# STM32L4_Lora.net
KiCad netlist of a schematic drawn in EAGLE
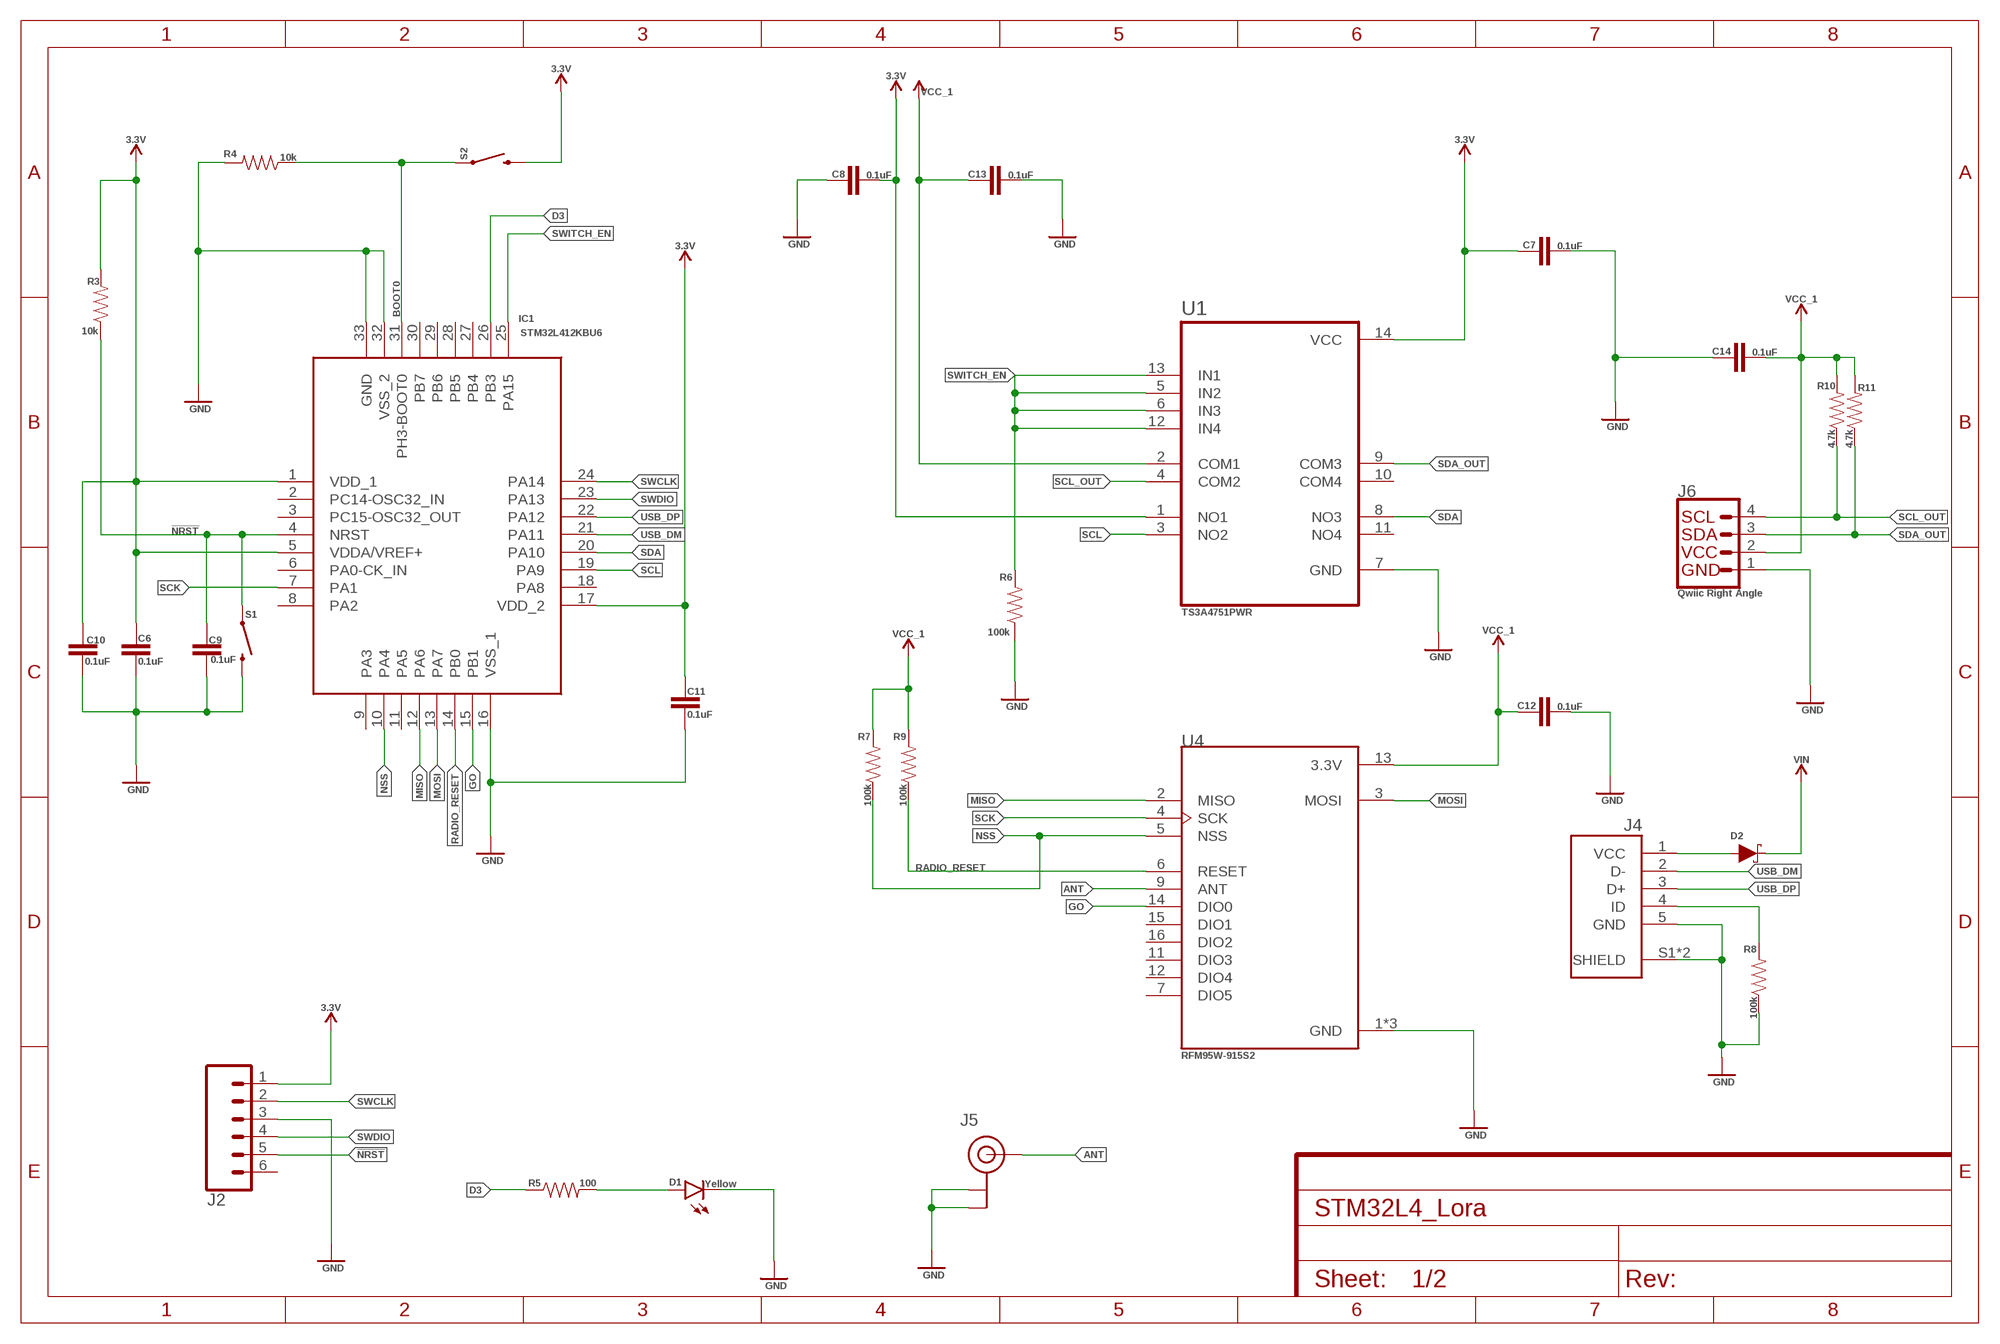
[diagram p0: schematic, sheet 1]
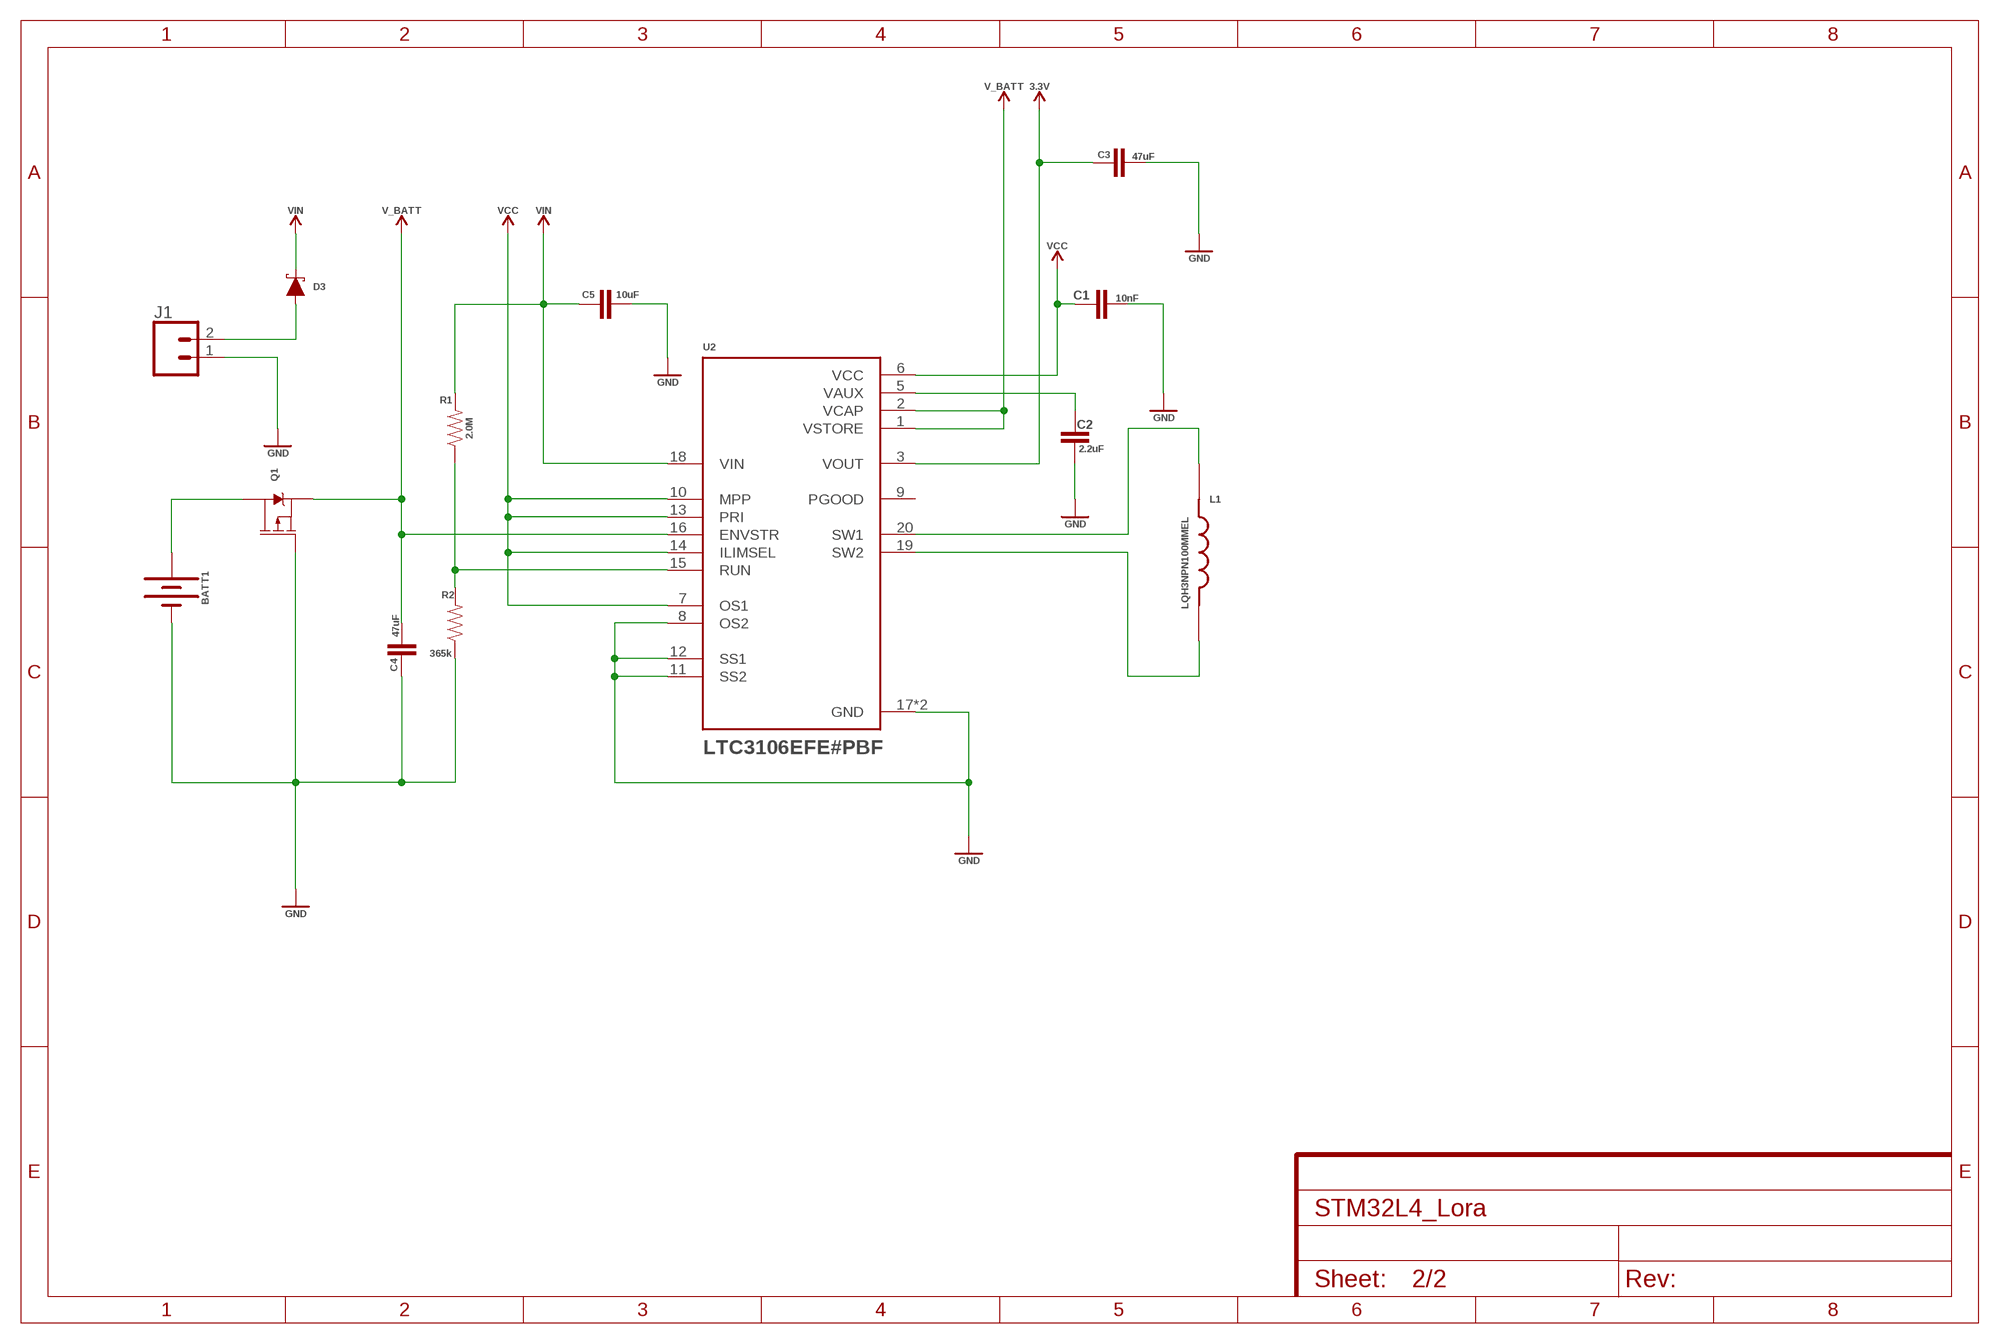
[diagram p1: schematic, sheet 2]

(export (version "E")
  (design (tool "Eeschema 10.0.6"))
  (components
    (comp (ref "C6")
      (value "0.1uF")
      (footprint "eagle-import:0603")
      (libsource (lib "eagle-import") (part "0.1UF-0603-25V-(+80/-20%)"))
    )
    (comp (ref "C7")
      (value "0.1uF")
      (footprint "eagle-import:0603")
      (libsource (lib "eagle-import") (part "0.1UF-0603-25V-(+80/-20%)"))
    )
    (comp (ref "C8")
      (value "0.1uF")
      (footprint "eagle-import:0603")
      (libsource (lib "eagle-import") (part "0.1UF-0603-25V-(+80/-20%)"))
    )
    (comp (ref "C9")
      (value "0.1uF")
      (footprint "eagle-import:0603")
      (libsource (lib "eagle-import") (part "0.1UF-0603-25V-(+80/-20%)"))
    )
    (comp (ref "C10")
      (value "0.1uF")
      (footprint "eagle-import:0603")
      (libsource (lib "eagle-import") (part "0.1UF-0603-25V-(+80/-20%)"))
    )
    (comp (ref "C11")
      (value "0.1uF")
      (footprint "eagle-import:0603")
      (libsource (lib "eagle-import") (part "0.1UF-0603-25V-(+80/-20%)"))
    )
    (comp (ref "C12")
      (value "0.1uF")
      (footprint "eagle-import:0603")
      (libsource (lib "eagle-import") (part "0.1UF-0603-25V-(+80/-20%)"))
    )
    (comp (ref "C13")
      (value "0.1uF")
      (footprint "eagle-import:0603")
      (libsource (lib "eagle-import") (part "0.1UF-0603-25V-(+80/-20%)"))
    )
    (comp (ref "C14")
      (value "0.1uF")
      (footprint "eagle-import:0603")
      (libsource (lib "eagle-import") (part "0.1UF-0603-25V-(+80/-20%)"))
    )
    (comp (ref "D1")
      (value "Yellow")
      (footprint "eagle-import:LED-0603")
      (libsource (lib "eagle-import") (part "LED-YELLOW0603"))
    )
    (comp (ref "D2")
      (value "120mA/40V/370mV")
      (footprint "eagle-import:SOD-523")
      (libsource (lib "eagle-import") (part "DIODE-SCHOTTKY-RB751S40"))
    )
    (comp (ref "IC1")
      (value "STM32L412KBU6")
      (footprint "eagle-import:QFN50P500X500X60-33N")
      (fields (field (name "MOUSER_PART_NUMBER") "511-STM32L412KBU6"))
      (libsource (lib "eagle-import") (part "STM32L412KBU6"))
    )
    (comp (ref "J2")
      (value "CONN_06LOCK_LONGPADS")
      (footprint "eagle-import:1X06_LOCK_LONGPADS")
      (libsource (lib "eagle-import") (part "CONN_06LOCK_LONGPADS"))
    )
    (comp (ref "J4")
      (value "USB3131-30-0230-A_REVB")
      (footprint "eagle-import:GCT_USB3131-30-0230-A_REVB")
      (fields (field (name "MF") "Global Connector Technology") (field (name "MP") "USB3131-30-0230-A"))
      (libsource (lib "eagle-import") (part "USB3131-30-0230-A_REVB"))
    )
    (comp (ref "J5")
      (value "U.FL")
      (footprint "eagle-import:U.FL")
      (libsource (lib "eagle-import") (part "U.FL"))
    )
    (comp (ref "J6")
      (value "Qwiic Right Angle")
      (footprint "eagle-import:1X04_1MM_RA")
      (libsource (lib "eagle-import") (part "I2C_STANDARDQWIIC"))
    )
    (comp (ref "R3")
      (value "10k")
      (footprint "eagle-import:0603")
      (libsource (lib "eagle-import") (part "10KOHM-0603-1/10W-1%"))
    )
    (comp (ref "R4")
      (value "10k")
      (footprint "eagle-import:0603")
      (libsource (lib "eagle-import") (part "10KOHM-0603-1/10W-1%"))
    )
    (comp (ref "R5")
      (value "100")
      (footprint "eagle-import:0603")
      (libsource (lib "eagle-import") (part "100OHM-0603-1/4W-5%"))
    )
    (comp (ref "R6")
      (value "100k")
      (footprint "eagle-import:0603")
      (libsource (lib "eagle-import") (part "100KOHM-0603-1/10W-1%"))
    )
    (comp (ref "R7")
      (value "100k")
      (footprint "eagle-import:0603")
      (libsource (lib "eagle-import") (part "100KOHM-0603-1/10W-1%"))
    )
    (comp (ref "R8")
      (value "100k")
      (footprint "eagle-import:0603")
      (libsource (lib "eagle-import") (part "100KOHM-0603-1/10W-1%"))
    )
    (comp (ref "R9")
      (value "100k")
      (footprint "eagle-import:0603")
      (libsource (lib "eagle-import") (part "100KOHM-0603-1/10W-1%"))
    )
    (comp (ref "R10")
      (value "4.7k")
      (footprint "eagle-import:0603")
      (libsource (lib "eagle-import") (part "4.7KOHM-0603-1/10W-1%"))
    )
    (comp (ref "R11")
      (value "4.7k")
      (footprint "eagle-import:0603")
      (libsource (lib "eagle-import") (part "4.7KOHM-0603-1/10W-1%"))
    )
    (comp (ref "S1")
      (value "MOMENTARY-SWITCH-SPST-SMD-4.6X2.8MM")
      (footprint "eagle-import:TACTILE_SWITCH_SMD_4.6X2.8MM")
      (libsource (lib "eagle-import") (part "MOMENTARY-SWITCH-SPST-SMD-4.6X2.8MM"))
    )
    (comp (ref "S2")
      (value "MOMENTARY-SWITCH-SPST-SMD-4.6X2.8MM")
      (footprint "eagle-import:TACTILE_SWITCH_SMD_4.6X2.8MM")
      (libsource (lib "eagle-import") (part "MOMENTARY-SWITCH-SPST-SMD-4.6X2.8MM"))
    )
    (comp (ref "U1")
      (value "TS3A4751PWR")
      (footprint "eagle-import:SOP65P640X120-14N")
      (fields (field (name "DIGI-KEY_PART_NUMBER") "296-20700-1-ND") (field (name "MF") "Texas Instruments"))
      (libsource (lib "eagle-import") (part "TS3A4751PWR"))
    )
    (comp (ref "U4")
      (value "RFM95W-915S2")
      (footprint "eagle-import:XCVR_RFM95W-915S2")
      (fields (field (name "MF") "RF Solutions"))
      (libsource (lib "eagle-import") (part "RFM95W-915S2"))
    )
    (comp (ref "BATT1")
      (value "KEYSTONE_54KEYSTONE_2")
      (footprint "eagle-import:KEYSTONE_V2")
      (libsource (lib "eagle-import") (part "KEYSTONE_54KEYSTONE_2"))
    )
    (comp (ref "C1")
      (value "10nF")
      (footprint "eagle-import:0603")
      (libsource (lib "eagle-import") (part "10NF-0603-50V-10%"))
    )
    (comp (ref "C2")
      (value "2.2uF")
      (footprint "eagle-import:0603")
      (libsource (lib "eagle-import") (part "2.2UF-0603-10V-20%"))
    )
    (comp (ref "C3")
      (value "47uF")
      (footprint "eagle-import:0603")
      (libsource (lib "eagle-import") (part "4.7UF0603"))
    )
    (comp (ref "C4")
      (value "47uF")
      (footprint "eagle-import:0603")
      (libsource (lib "eagle-import") (part "4.7UF0603"))
    )
    (comp (ref "C5")
      (value "10uF")
      (footprint "eagle-import:0603")
      (libsource (lib "eagle-import") (part "10UF-0603-6.3V-20%"))
    )
    (comp (ref "D3")
      (value "120mA/40V/370mV")
      (footprint "eagle-import:SOD-523")
      (libsource (lib "eagle-import") (part "DIODE-SCHOTTKY-RB751S40"))
    )
    (comp (ref "J1")
      (value "CONN_023.5MM")
      (footprint "eagle-import:SCREWTERMINAL-3.5MM-2")
      (libsource (lib "eagle-import") (part "CONN_023.5MM"))
    )
    (comp (ref "L1")
      (value "LQH3NPN100MMEL")
      (footprint "eagle-import:IND_LQH3NPN100MMEL")
      (fields (field (name "DIGI-KEY_PART_NUMBER") "490-15945-1-ND") (field (name "MF") "Murata"))
      (libsource (lib "eagle-import") (part "LQH3NPN100MMEL"))
    )
    (comp (ref "Q1")
      (value "2.5A/30V/105mΩ")
      (footprint "eagle-import:SOT23-3")
      (libsource (lib "eagle-import") (part "MOSFET_PCH-DMG2307L"))
    )
    (comp (ref "R1")
      (value "2.0M")
      (footprint "eagle-import:0603")
      (libsource (lib "eagle-import") (part "2MOHMS-0603-1/10W-1%"))
    )
    (comp (ref "R2")
      (value "365k")
      (footprint "eagle-import:0603")
      (libsource (lib "eagle-import") (part "390KOHM-0603-1/10W-1%"))
    )
    (comp (ref "U2")
      (value "LTC3106EFE#PBF")
      (footprint "eagle-import:SOP65P640X120-21N")
      (fields (field (name "MF") "Analog Devices"))
      (libsource (lib "eagle-import") (part "LTC3106EFE#PBF"))
    )
  )
  (nets
    (net (code "1") (name "3.3V") (class "Default")
      (node (ref "C10") (pin "1") (pinfunction "1_1") (pintype "passive"))
      (node (ref "C11") (pin "1") (pinfunction "1_1") (pintype "passive"))
      (node (ref "C3") (pin "1") (pinfunction "1_1") (pintype "passive"))
      (node (ref "C6") (pin "1") (pinfunction "1_1") (pintype "passive"))
      (node (ref "C7") (pin "1") (pinfunction "1_1") (pintype "passive"))
      (node (ref "C8") (pin "2") (pinfunction "2_2") (pintype "passive"))
      (node (ref "IC1") (pin "1") (pinfunction "VDD_1_1") (pintype "bidirectional"))
      (node (ref "IC1") (pin "17") (pinfunction "VDD_2_17") (pintype "bidirectional"))
      (node (ref "IC1") (pin "5") (pinfunction "VDDA/VREF+_5") (pintype "bidirectional"))
      (node (ref "J2") (pin "1") (pinfunction "1_1") (pintype "passive"))
      (node (ref "R3") (pin "2") (pinfunction "2_2") (pintype "passive"))
      (node (ref "S2") (pin "3") (pinfunction "2_3") (pintype "passive"))
      (node (ref "S2") (pin "4") (pinfunction "2_4") (pintype "passive"))
      (node (ref "U1") (pin "1") (pinfunction "NO1_1") (pintype "bidirectional"))
      (node (ref "U1") (pin "14") (pinfunction "VCC_14") (pintype "power_in"))
      (node (ref "U2") (pin "3") (pinfunction "VOUT_3") (pintype "output"))
    )
    (net (code "2") (name "ANT") (class "Default")
      (node (ref "J5") (pin "FEED") (pinfunction "SIGNAL_FEED") (pintype "bidirectional"))
      (node (ref "U4") (pin "9") (pinfunction "ANT_9") (pintype "bidirectional"))
    )
    (net (code "3") (name "BOOT0") (class "Default")
      (node (ref "IC1") (pin "31") (pinfunction "PH3-BOOT0_31") (pintype "bidirectional"))
      (node (ref "R4") (pin "1") (pinfunction "1_1") (pintype "passive"))
      (node (ref "S2") (pin "1") (pinfunction "1_1") (pintype "passive"))
      (node (ref "S2") (pin "2") (pinfunction "1_2") (pintype "passive"))
    )
    (net (code "4") (name "D3") (class "Default")
      (node (ref "IC1") (pin "26") (pinfunction "PB3_26") (pintype "bidirectional"))
      (node (ref "R5") (pin "1") (pinfunction "1_1") (pintype "passive"))
    )
    (net (code "5") (name "GND") (class "Default")
      (node (ref "BATT1") (pin "P$4") (pinfunction "-_P$4") (pintype "power_in"))
      (node (ref "BATT1") (pin "P$5") (pinfunction "-_P$5") (pintype "power_in"))
      (node (ref "BATT1") (pin "P$6") (pinfunction "-_P$6") (pintype "power_in"))
      (node (ref "C1") (pin "2") (pinfunction "2_2") (pintype "passive"))
      (node (ref "C10") (pin "2") (pinfunction "2_2") (pintype "passive"))
      (node (ref "C11") (pin "2") (pinfunction "2_2") (pintype "passive"))
      (node (ref "C12") (pin "2") (pinfunction "2_2") (pintype "passive"))
      (node (ref "C13") (pin "2") (pinfunction "2_2") (pintype "passive"))
      (node (ref "C14") (pin "1") (pinfunction "1_1") (pintype "passive"))
      (node (ref "C2") (pin "2") (pinfunction "2_2") (pintype "passive"))
      (node (ref "C3") (pin "2") (pinfunction "2_2") (pintype "passive"))
      (node (ref "C4") (pin "1") (pinfunction "1_1") (pintype "passive"))
      (node (ref "C5") (pin "2") (pinfunction "2_2") (pintype "passive"))
      (node (ref "C6") (pin "2") (pinfunction "2_2") (pintype "passive"))
      (node (ref "C7") (pin "2") (pinfunction "2_2") (pintype "passive"))
      (node (ref "C8") (pin "1") (pinfunction "1_1") (pintype "passive"))
      (node (ref "C9") (pin "2") (pinfunction "2_2") (pintype "passive"))
      (node (ref "D1") (pin "C") (pinfunction "C_C") (pintype "passive"))
      (node (ref "IC1") (pin "16") (pinfunction "VSS_1_16") (pintype "bidirectional"))
      (node (ref "IC1") (pin "32") (pinfunction "VSS_2_32") (pintype "bidirectional"))
      (node (ref "IC1") (pin "33") (pinfunction "GND_33") (pintype "bidirectional"))
      (node (ref "J1") (pin "1") (pinfunction "1_1") (pintype "passive"))
      (node (ref "J2") (pin "3") (pinfunction "3_3") (pintype "passive"))
      (node (ref "J4") (pin "5") (pinfunction "GND_5") (pintype "power_in"))
      (node (ref "J4") (pin "S1") (pinfunction "SHIELD_S1") (pintype "passive"))
      (node (ref "J4") (pin "S2") (pinfunction "SHIELD_S2") (pintype "passive"))
      (node (ref "J5") (pin "1") (pinfunction "GND_1") (pintype "bidirectional"))
      (node (ref "J5") (pin "2") (pinfunction "GND_2") (pintype "bidirectional"))
      (node (ref "J6") (pin "1") (pinfunction "1_1") (pintype "power_in"))
      (node (ref "Q1") (pin "1") (pinfunction "G_1") (pintype "bidirectional"))
      (node (ref "R2") (pin "1") (pinfunction "1_1") (pintype "passive"))
      (node (ref "R4") (pin "2") (pinfunction "2_2") (pintype "passive"))
      (node (ref "R6") (pin "1") (pinfunction "1_1") (pintype "passive"))
      (node (ref "R8") (pin "1") (pinfunction "1_1") (pintype "passive"))
      (node (ref "S1") (pin "3") (pinfunction "2_3") (pintype "passive"))
      (node (ref "S1") (pin "4") (pinfunction "2_4") (pintype "passive"))
      (node (ref "U1") (pin "7") (pinfunction "GND_7") (pintype "power_in"))
      (node (ref "U2") (pin "11") (pinfunction "SS2_11") (pintype "input"))
      (node (ref "U2") (pin "12") (pinfunction "SS1_12") (pintype "input"))
      (node (ref "U2") (pin "17") (pinfunction "GND_17") (pintype "power_in"))
      (node (ref "U2") (pin "21") (pinfunction "GND_21") (pintype "power_in"))
      (node (ref "U2") (pin "8") (pinfunction "OS2_8") (pintype "input"))
      (node (ref "U4") (pin "1") (pinfunction "GND_1") (pintype "power_in"))
      (node (ref "U4") (pin "10") (pinfunction "GND_10") (pintype "power_in"))
      (node (ref "U4") (pin "8") (pinfunction "GND_8") (pintype "power_in"))
    )
    (net (code "6") (name "GO") (class "Default")
      (node (ref "IC1") (pin "15") (pinfunction "PB1_15") (pintype "bidirectional"))
      (node (ref "U4") (pin "14") (pinfunction "DIO0_14") (pintype "bidirectional"))
    )
    (net (code "7") (name "MISO") (class "Default")
      (node (ref "IC1") (pin "12") (pinfunction "PA6_12") (pintype "bidirectional"))
      (node (ref "U4") (pin "2") (pinfunction "MISO_2") (pintype "input"))
    )
    (net (code "8") (name "MOSI") (class "Default")
      (node (ref "IC1") (pin "13") (pinfunction "PA7_13") (pintype "bidirectional"))
      (node (ref "U4") (pin "3") (pinfunction "MOSI_3") (pintype "output"))
    )
    (net (code "9") (name "NSS") (class "Default")
      (node (ref "IC1") (pin "10") (pinfunction "PA4_10") (pintype "bidirectional"))
      (node (ref "R7") (pin "1") (pinfunction "1_1") (pintype "passive"))
      (node (ref "U4") (pin "5") (pinfunction "NSS_5") (pintype "input"))
    )
    (net (code "10") (name "Net-(D1-PadA)") (class "Default")
      (node (ref "D1") (pin "A") (pinfunction "A_A") (pintype "passive"))
      (node (ref "R5") (pin "2") (pinfunction "2_2") (pintype "passive"))
    )
    (net (code "11") (name "Net-(D3-PadA)") (class "Default")
      (node (ref "D3") (pin "A") (pinfunction "A_A") (pintype "passive"))
      (node (ref "J1") (pin "2") (pinfunction "2_2") (pintype "passive"))
    )
    (net (code "12") (name "Net-(J4-ID)") (class "Default")
      (node (ref "J4") (pin "4") (pinfunction "ID_4") (pintype "bidirectional"))
      (node (ref "R8") (pin "2") (pinfunction "2_2") (pintype "passive"))
    )
    (net (code "13") (name "Net-(J4-VCC)") (class "Default")
      (node (ref "D2") (pin "A") (pinfunction "A_A") (pintype "passive"))
      (node (ref "J4") (pin "1") (pinfunction "VCC_1") (pintype "power_in"))
    )
    (net (code "14") (name "Net-(Q1-D)") (class "Default")
      (node (ref "BATT1") (pin "P$1") (pinfunction "+_P$1") (pintype "power_in"))
      (node (ref "BATT1") (pin "P$2") (pinfunction "+_P$2") (pintype "power_in"))
      (node (ref "BATT1") (pin "P$3") (pinfunction "+_P$3") (pintype "power_in"))
      (node (ref "Q1") (pin "3") (pinfunction "D_3") (pintype "bidirectional"))
    )
    (net (code "15") (name "Net-(U2-RUN)") (class "Default")
      (node (ref "R1") (pin "1") (pinfunction "1_1") (pintype "passive"))
      (node (ref "R2") (pin "2") (pinfunction "2_2") (pintype "passive"))
      (node (ref "U2") (pin "15") (pinfunction "RUN_15") (pintype "input"))
    )
    (net (code "16") (name "Net-(U2-SW1)") (class "Default")
      (node (ref "L1") (pin "1") (pinfunction "1_1") (pintype "passive"))
      (node (ref "U2") (pin "20") (pinfunction "SW1_20") (pintype "passive"))
    )
    (net (code "17") (name "Net-(U2-SW2)") (class "Default")
      (node (ref "L1") (pin "2") (pinfunction "2_2") (pintype "passive"))
      (node (ref "U2") (pin "19") (pinfunction "SW2_19") (pintype "passive"))
    )
    (net (code "18") (name "Net-(U2-VAUX)") (class "Default")
      (node (ref "C2") (pin "1") (pinfunction "1_1") (pintype "passive"))
      (node (ref "U2") (pin "5") (pinfunction "VAUX_5") (pintype "power_in"))
    )
    (net (code "19") (name "RADIO_RESET") (class "Default")
      (node (ref "IC1") (pin "14") (pinfunction "PB0_14") (pintype "bidirectional"))
      (node (ref "R9") (pin "1") (pinfunction "1_1") (pintype "passive"))
      (node (ref "U4") (pin "6") (pinfunction "RESET_6") (pintype "bidirectional"))
    )
    (net (code "20") (name "SCK") (class "Default")
      (node (ref "IC1") (pin "7") (pinfunction "PA1_7") (pintype "bidirectional"))
      (node (ref "U4") (pin "4") (pinfunction "SCK_4") (pintype "input"))
    )
    (net (code "21") (name "SCL") (class "Default")
      (node (ref "IC1") (pin "19") (pinfunction "PA9_19") (pintype "bidirectional"))
      (node (ref "U1") (pin "3") (pinfunction "NO2_3") (pintype "bidirectional"))
    )
    (net (code "22") (name "SCL_OUT") (class "Default")
      (node (ref "J6") (pin "4") (pinfunction "4_4") (pintype "passive"))
      (node (ref "R10") (pin "1") (pinfunction "1_1") (pintype "passive"))
      (node (ref "U1") (pin "4") (pinfunction "COM2_4") (pintype "bidirectional"))
    )
    (net (code "23") (name "SDA") (class "Default")
      (node (ref "IC1") (pin "20") (pinfunction "PA10_20") (pintype "bidirectional"))
      (node (ref "U1") (pin "8") (pinfunction "NO3_8") (pintype "bidirectional"))
    )
    (net (code "24") (name "SDA_OUT") (class "Default")
      (node (ref "J6") (pin "3") (pinfunction "3_3") (pintype "passive"))
      (node (ref "R11") (pin "1") (pinfunction "1_1") (pintype "passive"))
      (node (ref "U1") (pin "9") (pinfunction "COM3_9") (pintype "bidirectional"))
    )
    (net (code "25") (name "SWCLK") (class "Default")
      (node (ref "IC1") (pin "24") (pinfunction "PA14_24") (pintype "bidirectional"))
      (node (ref "J2") (pin "2") (pinfunction "2_2") (pintype "passive"))
    )
    (net (code "26") (name "SWDIO") (class "Default")
      (node (ref "IC1") (pin "23") (pinfunction "PA13_23") (pintype "bidirectional"))
      (node (ref "J2") (pin "4") (pinfunction "4_4") (pintype "passive"))
    )
    (net (code "27") (name "SWITCH_EN") (class "Default")
      (node (ref "IC1") (pin "25") (pinfunction "PA15_25") (pintype "bidirectional"))
      (node (ref "R6") (pin "2") (pinfunction "2_2") (pintype "passive"))
      (node (ref "U1") (pin "12") (pinfunction "IN4_12") (pintype "input"))
      (node (ref "U1") (pin "13") (pinfunction "IN1_13") (pintype "input"))
      (node (ref "U1") (pin "5") (pinfunction "IN2_5") (pintype "input"))
      (node (ref "U1") (pin "6") (pinfunction "IN3_6") (pintype "input"))
    )
    (net (code "28") (name "USB_DM") (class "Default")
      (node (ref "IC1") (pin "21") (pinfunction "PA11_21") (pintype "bidirectional"))
      (node (ref "J4") (pin "2") (pinfunction "D-_2") (pintype "bidirectional"))
    )
    (net (code "29") (name "USB_DP") (class "Default")
      (node (ref "IC1") (pin "22") (pinfunction "PA12_22") (pintype "bidirectional"))
      (node (ref "J4") (pin "3") (pinfunction "D+_3") (pintype "bidirectional"))
    )
    (net (code "30") (name "VCC") (class "Default")
      (node (ref "C1") (pin "1") (pinfunction "1_1") (pintype "passive"))
      (node (ref "U2") (pin "10") (pinfunction "MPP_10") (pintype "input"))
      (node (ref "U2") (pin "13") (pinfunction "PRI_13") (pintype "input"))
      (node (ref "U2") (pin "14") (pinfunction "ILIMSEL_14") (pintype "input"))
      (node (ref "U2") (pin "6") (pinfunction "VCC_6") (pintype "power_in"))
      (node (ref "U2") (pin "7") (pinfunction "OS1_7") (pintype "input"))
    )
    (net (code "31") (name "VCC_1") (class "Default")
      (node (ref "C12") (pin "1") (pinfunction "1_1") (pintype "passive"))
      (node (ref "C13") (pin "1") (pinfunction "1_1") (pintype "passive"))
      (node (ref "C14") (pin "2") (pinfunction "2_2") (pintype "passive"))
      (node (ref "J6") (pin "2") (pinfunction "2_2") (pintype "power_in"))
      (node (ref "R10") (pin "2") (pinfunction "2_2") (pintype "passive"))
      (node (ref "R11") (pin "2") (pinfunction "2_2") (pintype "passive"))
      (node (ref "R7") (pin "2") (pinfunction "2_2") (pintype "passive"))
      (node (ref "R9") (pin "2") (pinfunction "2_2") (pintype "passive"))
      (node (ref "U1") (pin "2") (pinfunction "COM1_2") (pintype "bidirectional"))
      (node (ref "U4") (pin "13") (pinfunction "3.3V_13") (pintype "power_in"))
    )
    (net (code "32") (name "VIN") (class "Default")
      (node (ref "C5") (pin "1") (pinfunction "1_1") (pintype "passive"))
      (node (ref "D2") (pin "C") (pinfunction "C_C") (pintype "passive"))
      (node (ref "D3") (pin "C") (pinfunction "C_C") (pintype "passive"))
      (node (ref "R1") (pin "2") (pinfunction "2_2") (pintype "passive"))
      (node (ref "U2") (pin "18") (pinfunction "VIN_18") (pintype "input"))
    )
    (net (code "33") (name "V_BATT") (class "Default")
      (node (ref "C4") (pin "2") (pinfunction "2_2") (pintype "passive"))
      (node (ref "Q1") (pin "2") (pinfunction "S_2") (pintype "bidirectional"))
      (node (ref "U2") (pin "1") (pinfunction "VSTORE_1") (pintype "power_in"))
      (node (ref "U2") (pin "16") (pinfunction "ENVSTR_16") (pintype "input"))
      (node (ref "U2") (pin "2") (pinfunction "VCAP_2") (pintype "power_in"))
    )
    (net (code "34") (name "unconnected-(IC1-PA0-CK_IN-Pad6)") (class "Default")
      (node (ref "IC1") (pin "6") (pinfunction "PA0-CK_IN_6") (pintype "bidirectional"))
    )
    (net (code "35") (name "unconnected-(IC1-PA2-Pad8)") (class "Default")
      (node (ref "IC1") (pin "8") (pinfunction "PA2_8") (pintype "bidirectional"))
    )
    (net (code "36") (name "unconnected-(IC1-PA3-Pad9)") (class "Default")
      (node (ref "IC1") (pin "9") (pinfunction "PA3_9") (pintype "bidirectional"))
    )
    (net (code "37") (name "unconnected-(IC1-PA5-Pad11)") (class "Default")
      (node (ref "IC1") (pin "11") (pinfunction "PA5_11") (pintype "bidirectional"))
    )
    (net (code "38") (name "unconnected-(IC1-PA8-Pad18)") (class "Default")
      (node (ref "IC1") (pin "18") (pinfunction "PA8_18") (pintype "bidirectional"))
    )
    (net (code "39") (name "unconnected-(IC1-PB4-Pad27)") (class "Default")
      (node (ref "IC1") (pin "27") (pinfunction "PB4_27") (pintype "bidirectional"))
    )
    (net (code "40") (name "unconnected-(IC1-PB5-Pad28)") (class "Default")
      (node (ref "IC1") (pin "28") (pinfunction "PB5_28") (pintype "bidirectional"))
    )
    (net (code "41") (name "unconnected-(IC1-PB6-Pad29)") (class "Default")
      (node (ref "IC1") (pin "29") (pinfunction "PB6_29") (pintype "bidirectional"))
    )
    (net (code "42") (name "unconnected-(IC1-PB7-Pad30)") (class "Default")
      (node (ref "IC1") (pin "30") (pinfunction "PB7_30") (pintype "bidirectional"))
    )
    (net (code "43") (name "unconnected-(IC1-PC14-OSC32_IN-Pad2)") (class "Default")
      (node (ref "IC1") (pin "2") (pinfunction "PC14-OSC32_IN_2") (pintype "bidirectional"))
    )
    (net (code "44") (name "unconnected-(IC1-PC15-OSC32_OUT-Pad3)") (class "Default")
      (node (ref "IC1") (pin "3") (pinfunction "PC15-OSC32_OUT_3") (pintype "bidirectional"))
    )
    (net (code "45") (name "unconnected-(J2-Pad6)") (class "Default")
      (node (ref "J2") (pin "6") (pinfunction "6_6") (pintype "passive"))
    )
    (net (code "46") (name "unconnected-(U1-COM4-Pad10)") (class "Default")
      (node (ref "U1") (pin "10") (pinfunction "COM4_10") (pintype "bidirectional"))
    )
    (net (code "47") (name "unconnected-(U1-NO4-Pad11)") (class "Default")
      (node (ref "U1") (pin "11") (pinfunction "NO4_11") (pintype "bidirectional"))
    )
    (net (code "48") (name "unconnected-(U2-PGOOD-Pad9)") (class "Default")
      (node (ref "U2") (pin "9") (pinfunction "PGOOD_9") (pintype "output"))
    )
    (net (code "49") (name "unconnected-(U4-DIO1-Pad15)") (class "Default")
      (node (ref "U4") (pin "15") (pinfunction "DIO1_15") (pintype "bidirectional"))
    )
    (net (code "50") (name "unconnected-(U4-DIO2-Pad16)") (class "Default")
      (node (ref "U4") (pin "16") (pinfunction "DIO2_16") (pintype "bidirectional"))
    )
    (net (code "51") (name "unconnected-(U4-DIO3-Pad11)") (class "Default")
      (node (ref "U4") (pin "11") (pinfunction "DIO3_11") (pintype "bidirectional"))
    )
    (net (code "52") (name "unconnected-(U4-DIO4-Pad12)") (class "Default")
      (node (ref "U4") (pin "12") (pinfunction "DIO4_12") (pintype "bidirectional"))
    )
    (net (code "53") (name "unconnected-(U4-DIO5-Pad7)") (class "Default")
      (node (ref "U4") (pin "7") (pinfunction "DIO5_7") (pintype "bidirectional"))
    )
    (net (code "54") (name "~{NRST}") (class "Default")
      (node (ref "C9") (pin "1") (pinfunction "1_1") (pintype "passive"))
      (node (ref "IC1") (pin "4") (pinfunction "NRST_4") (pintype "bidirectional"))
      (node (ref "J2") (pin "5") (pinfunction "5_5") (pintype "passive"))
      (node (ref "R3") (pin "1") (pinfunction "1_1") (pintype "passive"))
      (node (ref "S1") (pin "1") (pinfunction "1_1") (pintype "passive"))
      (node (ref "S1") (pin "2") (pinfunction "1_2") (pintype "passive"))
    )
  )
)
